# DM1098EMB_USB.net
KiCad netlist of a schematic drawn in Altium Designer
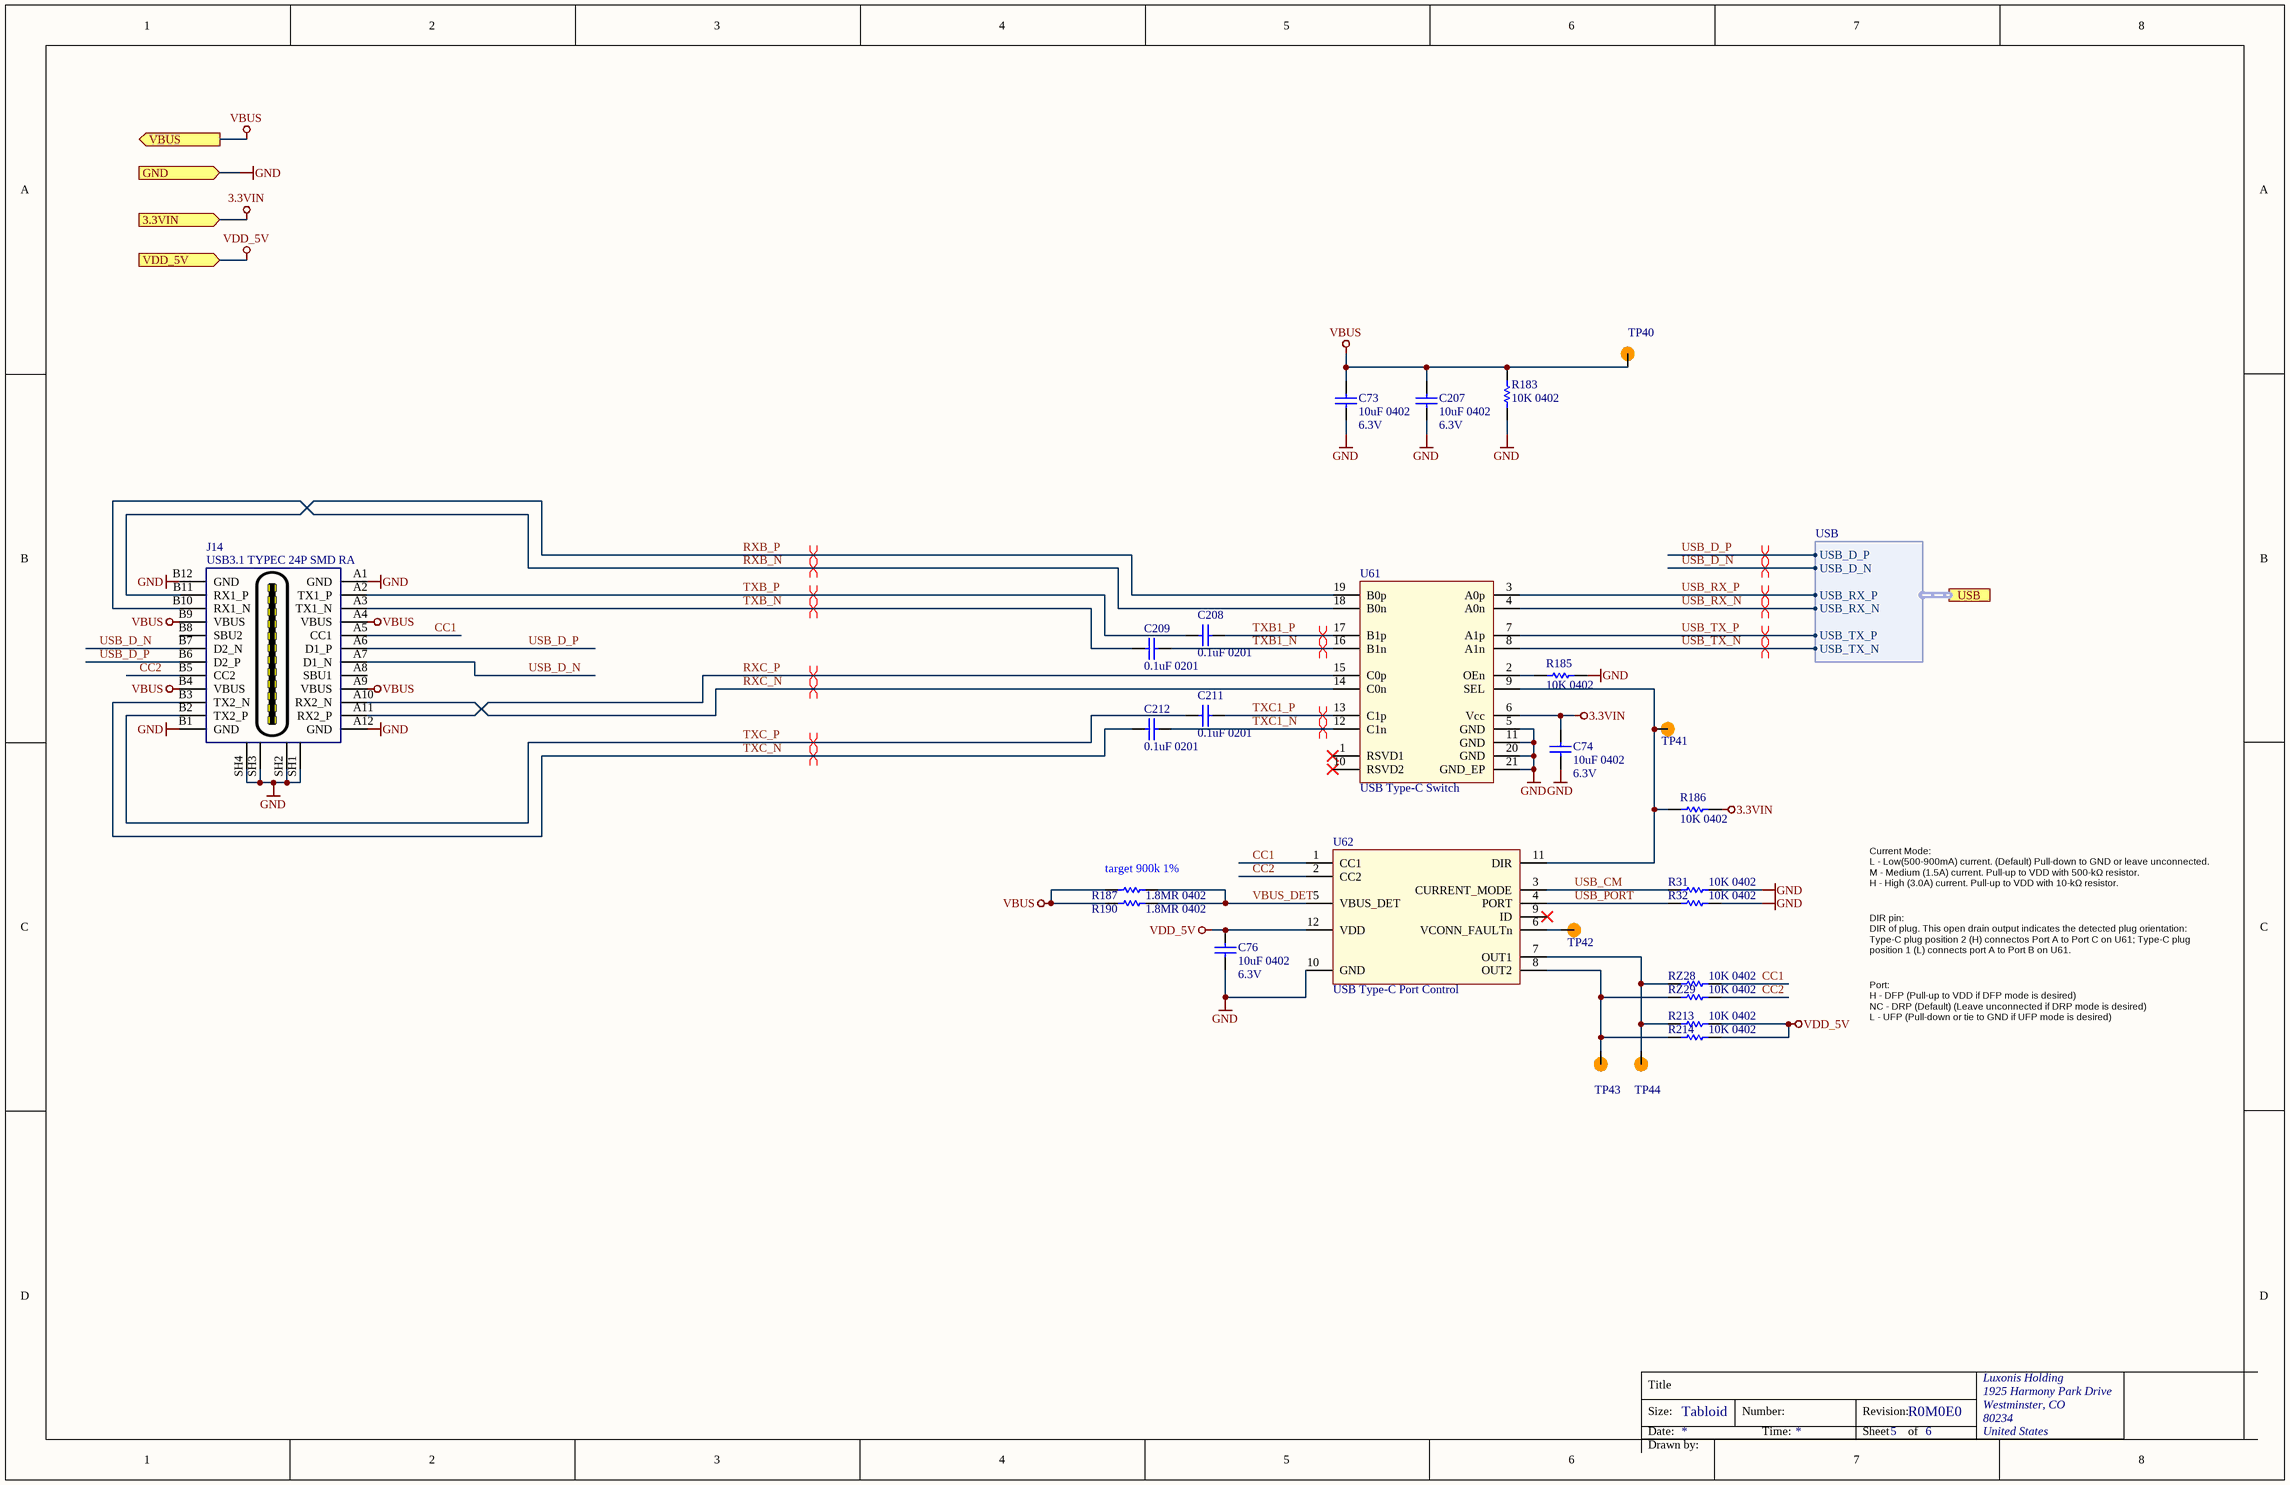
[diagram p0: DM1098EMB_USB.SchDoc]

(export (version "E")
  (design (tool "Eeschema 10.0.6"))
  (components
    (comp (ref "C73")
      (value "10uF 0402")
      (footprint "CAP_Altium_Vault_Generic:CAPC0402(1005)70_N")
      (description "CAP CER 10UF 6.3V X5R 0402 20%")
      (fields (field (name "TOLERANCE") "20%") (field (name "VOLTAGE RATING") "6.3V"))
      (libsource (lib "LuxonisMaster") (part "GRM155R60J106ME15D"))
    )
    (comp (ref "C74")
      (value "10uF 0402")
      (footprint "CAP_Altium_Vault_Generic:CAPC0402(1005)70_N")
      (description "CAP CER 10UF 6.3V X5R 0402 20%")
      (fields (field (name "TOLERANCE") "20%") (field (name "VOLTAGE RATING") "6.3V"))
      (libsource (lib "LuxonisMaster") (part "GRM155R60J106ME15D"))
    )
    (comp (ref "C76")
      (value "10uF 0402")
      (footprint "CAP_Altium_Vault_Generic:CAPC0402(1005)70_N")
      (description "CAP CER 10UF 6.3V X5R 0402 20%")
      (fields (field (name "TOLERANCE") "20%") (field (name "VOLTAGE RATING") "6.3V"))
      (libsource (lib "LuxonisMaster") (part "GRM155R60J106ME15D"))
    )
    (comp (ref "C207")
      (value "10uF 0402")
      (footprint "CAP_Altium_Vault_Generic:CAPC0402(1005)70_N")
      (description "CAP CER 10UF 6.3V X5R 0402 20%")
      (fields (field (name "TOLERANCE") "20%") (field (name "VOLTAGE RATING") "6.3V"))
      (libsource (lib "LuxonisMaster") (part "GRM155R60J106ME15D"))
    )
    (comp (ref "C208")
      (value "0.1uF 0201")
      (footprint "CAP_Altium_Vault_Generic:CAPC0201(0603)33_L")
      (description "CAP CER 0.1UF 10V X5R 0201")
      (fields (field (name "TOLERANCE") "10%") (field (name "VOLTAGE") "10V"))
      (libsource (lib "LuxonisMaster") (part "GRM033R61A104KE15D"))
    )
    (comp (ref "C209")
      (value "0.1uF 0201")
      (footprint "CAP_Altium_Vault_Generic:CAPC0201(0603)33_L")
      (description "CAP CER 0.1UF 10V X5R 0201")
      (fields (field (name "TOLERANCE") "10%") (field (name "VOLTAGE") "10V"))
      (libsource (lib "LuxonisMaster") (part "GRM033R61A104KE15D"))
    )
    (comp (ref "C211")
      (value "0.1uF 0201")
      (footprint "CAP_Altium_Vault_Generic:CAPC0201(0603)33_L")
      (description "CAP CER 0.1UF 10V X5R 0201")
      (fields (field (name "TOLERANCE") "10%") (field (name "VOLTAGE") "10V"))
      (libsource (lib "LuxonisMaster") (part "GRM033R61A104KE15D"))
    )
    (comp (ref "C212")
      (value "0.1uF 0201")
      (footprint "CAP_Altium_Vault_Generic:CAPC0201(0603)33_L")
      (description "CAP CER 0.1UF 10V X5R 0201")
      (fields (field (name "TOLERANCE") "10%") (field (name "VOLTAGE") "10V"))
      (libsource (lib "LuxonisMaster") (part "GRM033R61A104KE15D"))
    )
    (comp (ref "J14")
      (value "USB3.1 TYPEC 24P SMD RA")
      (footprint "LuxonisMaster:105450-0101")
      (description "CONN RCP USB3.1 TYPEC 24P SMD RA")
      (libsource (lib "LuxonisMaster") (part "105450-0101"))
    )
    (comp (ref "R31")
      (value "10K 0402")
      (footprint "RES_Altium_Vault_Generic:RESC0402(1005)_N")
      (fields (field (name "TOLERANCE") "1%"))
      (libsource (lib "LuxonisMaster") (part "RC0402FR-1310KL"))
    )
    (comp (ref "R32")
      (value "10K 0402")
      (footprint "RES_Altium_Vault_Generic:RESC0402(1005)_N")
      (fields (field (name "TOLERANCE") "1%"))
      (libsource (lib "LuxonisMaster") (part "RC0402FR-1310KL"))
    )
    (comp (ref "R183")
      (value "10K 0402")
      (footprint "RES_Altium_Vault_Generic:RESC0402(1005)_N")
      (fields (field (name "TOLERANCE") "1%"))
      (libsource (lib "LuxonisMaster") (part "RC0402FR-1310KL"))
    )
    (comp (ref "R185")
      (value "10K 0402")
      (footprint "RES_Altium_Vault_Generic:RESC0402(1005)_N")
      (fields (field (name "TOLERANCE") "1%"))
      (libsource (lib "LuxonisMaster") (part "RC0402FR-1310KL"))
    )
    (comp (ref "R186")
      (value "10K 0402")
      (footprint "RES_Altium_Vault_Generic:RESC0402(1005)_N")
      (fields (field (name "TOLERANCE") "1%"))
      (libsource (lib "LuxonisMaster") (part "RC0402FR-1310KL"))
    )
    (comp (ref "R187")
      (value "1.8MR 0402")
      (footprint "RES_Altium_Vault_Generic:RESC0402(1005)_N")
      (description "RES SMD 1.8M OHM 1% 1/16W 0402")
      (fields (field (name "TOLERANCE") "1%"))
      (libsource (lib "LuxonisMaster") (part "CRCW04021M80FKED"))
    )
    (comp (ref "R190")
      (value "1.8MR 0402")
      (footprint "RES_Altium_Vault_Generic:RESC0402(1005)_N")
      (description "RES SMD 1.8M OHM 1% 1/16W 0402")
      (fields (field (name "TOLERANCE") "1%"))
      (libsource (lib "LuxonisMaster") (part "CRCW04021M80FKED"))
    )
    (comp (ref "R213")
      (value "10K 0402")
      (footprint "RES_Altium_Vault_Generic:RESC0402(1005)_N")
      (fields (field (name "TOLERANCE") "1%"))
      (libsource (lib "LuxonisMaster") (part "RC0402FR-1310KL"))
    )
    (comp (ref "R214")
      (value "10K 0402")
      (footprint "RES_Altium_Vault_Generic:RESC0402(1005)_N")
      (fields (field (name "TOLERANCE") "1%"))
      (libsource (lib "LuxonisMaster") (part "RC0402FR-1310KL"))
    )
    (comp (ref "RZ28")
      (value "10K 0402")
      (footprint "RES_Altium_Vault_Generic:RESC0402(1005)_N")
      (fields (field (name "TOLERANCE") "1%"))
      (libsource (lib "LuxonisMaster") (part "RC0402FR-1310KL"))
    )
    (comp (ref "RZ29")
      (value "10K 0402")
      (footprint "RES_Altium_Vault_Generic:RESC0402(1005)_N")
      (fields (field (name "TOLERANCE") "1%"))
      (libsource (lib "LuxonisMaster") (part "RC0402FR-1310KL"))
    )
    (comp (ref "TP40")
      (value "TP100_200_NS")
      (footprint "LuxonisMaster:TP100_200_NS")
      (libsource (lib "LuxonisMaster") (part "TEST_POINT"))
    )
    (comp (ref "TP41")
      (value "TP100_200_NS")
      (footprint "LuxonisMaster:TP100_200_NS")
      (libsource (lib "LuxonisMaster") (part "TEST_POINT"))
    )
    (comp (ref "TP42")
      (value "TP100_200_NS")
      (footprint "LuxonisMaster:TP100_200_NS")
      (libsource (lib "LuxonisMaster") (part "TEST_POINT"))
    )
    (comp (ref "TP43")
      (value "TP100_200_NS")
      (footprint "LuxonisMaster:TP100_200_NS")
      (libsource (lib "LuxonisMaster") (part "TEST_POINT"))
    )
    (comp (ref "TP44")
      (value "TP100_200_NS")
      (footprint "LuxonisMaster:TP100_200_NS")
      (libsource (lib "LuxonisMaster") (part "TEST_POINT"))
    )
    (comp (ref "U61")
      (value "USB Type-C Switch")
      (footprint "LuxonisMaster:HD3SS3212RKSR")
      (description "IC MUX 2:1 8 OHM 20VQFN")
      (libsource (lib "LuxonisMaster") (part "HD3SS3212RKSR"))
    )
    (comp (ref "U62")
      (value "USB Type-C Port Control")
      (footprint "LuxonisMaster:TUSB321RWBR")
      (description "IC USB PORT CONTROL TYPE-C 12X2Q")
      (libsource (lib "LuxonisMaster") (part "TUSB321RWBR"))
    )
  )
  (nets
    (net (code "2") (name "/CC1") (class "Default")
      (node (ref "J14") (pin "A5") (pinfunction "CC1_A5") (pintype "passive"))
      (node (ref "RZ28") (pin "2") (pinfunction "2_2") (pintype "passive"))
      (node (ref "U62") (pin "1") (pinfunction "CC1_1") (pintype "passive"))
    )
    (net (code "3") (name "/CC2") (class "Default")
      (node (ref "J14") (pin "B5") (pinfunction "CC2_B5") (pintype "passive"))
      (node (ref "RZ29") (pin "2") (pinfunction "2_2") (pintype "passive"))
      (node (ref "U62") (pin "2") (pinfunction "CC2_2") (pintype "passive"))
    )
    (net (code "4") (name "/RXB_N") (class "Default")
      (node (ref "J14") (pin "B10") (pinfunction "RX1_N_B10") (pintype "passive"))
      (node (ref "U61") (pin "18") (pinfunction "B0n_18") (pintype "passive"))
    )
    (net (code "5") (name "/RXB_P") (class "Default")
      (node (ref "J14") (pin "B11") (pinfunction "RX1_P_B11") (pintype "passive"))
      (node (ref "U61") (pin "19") (pinfunction "B0p_19") (pintype "passive"))
    )
    (net (code "6") (name "/RXC_N") (class "Default")
      (node (ref "J14") (pin "A10") (pinfunction "RX2_N_A10") (pintype "passive"))
      (node (ref "U61") (pin "14") (pinfunction "C0n_14") (pintype "passive"))
    )
    (net (code "7") (name "/RXC_P") (class "Default")
      (node (ref "J14") (pin "A11") (pinfunction "RX2_P_A11") (pintype "passive"))
      (node (ref "U61") (pin "15") (pinfunction "C0p_15") (pintype "passive"))
    )
    (net (code "8") (name "/TXB1_N") (class "Default")
      (node (ref "C209") (pin "2") (pinfunction "2_2") (pintype "passive"))
      (node (ref "U61") (pin "16") (pinfunction "B1n_16") (pintype "passive"))
    )
    (net (code "9") (name "/TXB1_P") (class "Default")
      (node (ref "C208") (pin "2") (pinfunction "2_2") (pintype "passive"))
      (node (ref "U61") (pin "17") (pinfunction "B1p_17") (pintype "passive"))
    )
    (net (code "10") (name "/TXB_N") (class "Default")
      (node (ref "C209") (pin "1") (pinfunction "1_1") (pintype "passive"))
      (node (ref "J14") (pin "A3") (pinfunction "TX1_N_A3") (pintype "passive"))
    )
    (net (code "11") (name "/TXB_P") (class "Default")
      (node (ref "C208") (pin "1") (pinfunction "1_1") (pintype "passive"))
      (node (ref "J14") (pin "A2") (pinfunction "TX1_P_A2") (pintype "passive"))
    )
    (net (code "12") (name "/TXC1_N") (class "Default")
      (node (ref "C212") (pin "2") (pinfunction "2_2") (pintype "passive"))
      (node (ref "U61") (pin "12") (pinfunction "C1n_12") (pintype "passive"))
    )
    (net (code "13") (name "/TXC1_P") (class "Default")
      (node (ref "C211") (pin "2") (pinfunction "2_2") (pintype "passive"))
      (node (ref "U61") (pin "13") (pinfunction "C1p_13") (pintype "passive"))
    )
    (net (code "14") (name "/TXC_N") (class "Default")
      (node (ref "C212") (pin "1") (pinfunction "1_1") (pintype "passive"))
      (node (ref "J14") (pin "B3") (pinfunction "TX2_N_B3") (pintype "passive"))
    )
    (net (code "15") (name "/TXC_P") (class "Default")
      (node (ref "C211") (pin "1") (pinfunction "1_1") (pintype "passive"))
      (node (ref "J14") (pin "B2") (pinfunction "TX2_P_B2") (pintype "passive"))
    )
    (net (code "16") (name "/USB_CM") (class "Default")
      (node (ref "R31") (pin "1") (pinfunction "1_1") (pintype "passive"))
      (node (ref "U62") (pin "3") (pinfunction "CURRENT_MODE_3") (pintype "passive"))
    )
    (net (code "17") (name "/USB_D_N") (class "Default")
      (node (ref "J14") (pin "A7") (pinfunction "D1_N_A7") (pintype "passive"))
      (node (ref "J14") (pin "B7") (pinfunction "D2_N_B7") (pintype "passive"))
    )
    (net (code "18") (name "/USB_D_P") (class "Default")
      (node (ref "J14") (pin "A6") (pinfunction "D1_P_A6") (pintype "passive"))
      (node (ref "J14") (pin "B6") (pinfunction "D2_P_B6") (pintype "passive"))
    )
    (net (code "19") (name "/USB_PORT") (class "Default")
      (node (ref "R32") (pin "1") (pinfunction "1_1") (pintype "passive"))
      (node (ref "U62") (pin "4") (pinfunction "PORT_4") (pintype "passive"))
    )
    (net (code "20") (name "/USB_RX_N") (class "Default")
      (node (ref "U61") (pin "4") (pinfunction "A0n_4") (pintype "passive"))
    )
    (net (code "21") (name "/USB_RX_P") (class "Default")
      (node (ref "U61") (pin "3") (pinfunction "A0p_3") (pintype "passive"))
    )
    (net (code "22") (name "/USB_TX_N") (class "Default")
      (node (ref "U61") (pin "8") (pinfunction "A1n_8") (pintype "passive"))
    )
    (net (code "23") (name "/USB_TX_P") (class "Default")
      (node (ref "U61") (pin "7") (pinfunction "A1p_7") (pintype "passive"))
    )
    (net (code "24") (name "/VBUS_DET") (class "Default")
      (node (ref "R187") (pin "2") (pinfunction "2_2") (pintype "passive"))
      (node (ref "R190") (pin "2") (pinfunction "2_2") (pintype "passive"))
      (node (ref "U62") (pin "5") (pinfunction "VBUS_DET_5") (pintype "passive"))
    )
    (net (code "26") (name "3.3VIN") (class "Default")
      (node (ref "C74") (pin "2") (pinfunction "2_2") (pintype "passive"))
      (node (ref "R186") (pin "2") (pinfunction "2_2") (pintype "passive"))
      (node (ref "U61") (pin "6") (pinfunction "Vcc_6") (pintype "passive"))
    )
    (net (code "27") (name "GND") (class "Default")
      (node (ref "C207") (pin "1") (pinfunction "1_1") (pintype "passive"))
      (node (ref "C73") (pin "1") (pinfunction "1_1") (pintype "passive"))
      (node (ref "C74") (pin "1") (pinfunction "1_1") (pintype "passive"))
      (node (ref "C76") (pin "1") (pinfunction "1_1") (pintype "passive"))
      (node (ref "J14") (pin "A1") (pinfunction "GND_A1") (pintype "passive"))
      (node (ref "J14") (pin "A12") (pinfunction "GND_A12") (pintype "passive"))
      (node (ref "J14") (pin "B1") (pinfunction "GND_B1") (pintype "passive"))
      (node (ref "J14") (pin "B12") (pinfunction "GND_B12") (pintype "passive"))
      (node (ref "J14") (pin "SH1") (pinfunction "SH_SH1") (pintype "passive"))
      (node (ref "J14") (pin "SH2") (pinfunction "SH_SH2") (pintype "passive"))
      (node (ref "J14") (pin "SH3") (pinfunction "SH_SH3") (pintype "passive"))
      (node (ref "J14") (pin "SH4") (pinfunction "SH_SH4") (pintype "passive"))
      (node (ref "R183") (pin "1") (pinfunction "1_1") (pintype "passive"))
      (node (ref "R185") (pin "2") (pinfunction "2_2") (pintype "passive"))
      (node (ref "R31") (pin "2") (pinfunction "2_2") (pintype "passive"))
      (node (ref "R32") (pin "2") (pinfunction "2_2") (pintype "passive"))
      (node (ref "U61") (pin "11") (pinfunction "GND_11") (pintype "passive"))
      (node (ref "U61") (pin "20") (pinfunction "GND_20") (pintype "passive"))
      (node (ref "U61") (pin "21") (pinfunction "GND_EP_21") (pintype "passive"))
      (node (ref "U61") (pin "5") (pinfunction "GND_5") (pintype "passive"))
      (node (ref "U62") (pin "10") (pinfunction "GND_10") (pintype "passive"))
    )
    (net (code "28") (name "Net-(U61-OEn)") (class "Default")
      (node (ref "R185") (pin "1") (pinfunction "1_1") (pintype "passive"))
      (node (ref "U61") (pin "2") (pinfunction "OEn_2") (pintype "passive"))
    )
    (net (code "29") (name "Net-(U61-SEL)") (class "Default")
      (node (ref "R186") (pin "1") (pinfunction "1_1") (pintype "passive"))
      (node (ref "TP41") (pin "1") (pintype "passive"))
      (node (ref "U61") (pin "9") (pinfunction "SEL_9") (pintype "passive"))
      (node (ref "U62") (pin "11") (pinfunction "DIR_11") (pintype "passive"))
    )
    (net (code "30") (name "Net-(U62-OUT1)") (class "Default")
      (node (ref "R213") (pin "1") (pinfunction "1_1") (pintype "passive"))
      (node (ref "RZ28") (pin "1") (pinfunction "1_1") (pintype "passive"))
      (node (ref "TP44") (pin "1") (pintype "passive"))
      (node (ref "U62") (pin "7") (pinfunction "OUT1_7") (pintype "passive"))
    )
    (net (code "31") (name "Net-(U62-OUT2)") (class "Default")
      (node (ref "R214") (pin "1") (pinfunction "1_1") (pintype "passive"))
      (node (ref "RZ29") (pin "1") (pinfunction "1_1") (pintype "passive"))
      (node (ref "TP43") (pin "1") (pintype "passive"))
      (node (ref "U62") (pin "8") (pinfunction "OUT2_8") (pintype "passive"))
    )
    (net (code "32") (name "Net-(U62-VCONN_FAULTn)") (class "Default")
      (node (ref "TP42") (pin "1") (pintype "passive"))
      (node (ref "U62") (pin "6") (pinfunction "VCONN_FAULTn_6") (pintype "passive"))
    )
    (net (code "33") (name "VBUS") (class "Default")
      (node (ref "C207") (pin "2") (pinfunction "2_2") (pintype "passive"))
      (node (ref "C73") (pin "2") (pinfunction "2_2") (pintype "passive"))
      (node (ref "J14") (pin "A4") (pinfunction "VBUS_A4") (pintype "passive"))
      (node (ref "J14") (pin "A9") (pinfunction "VBUS_A9") (pintype "passive"))
      (node (ref "J14") (pin "B4") (pinfunction "VBUS_B4") (pintype "passive"))
      (node (ref "J14") (pin "B9") (pinfunction "VBUS_B9") (pintype "passive"))
      (node (ref "R183") (pin "2") (pinfunction "2_2") (pintype "passive"))
      (node (ref "R187") (pin "1") (pinfunction "1_1") (pintype "passive"))
      (node (ref "R190") (pin "1") (pinfunction "1_1") (pintype "passive"))
      (node (ref "TP40") (pin "1") (pintype "passive"))
    )
    (net (code "34") (name "VDD_5V") (class "Default")
      (node (ref "C76") (pin "2") (pinfunction "2_2") (pintype "passive"))
      (node (ref "R213") (pin "2") (pinfunction "2_2") (pintype "passive"))
      (node (ref "R214") (pin "2") (pinfunction "2_2") (pintype "passive"))
      (node (ref "U62") (pin "12") (pinfunction "VDD_12") (pintype "passive"))
    )
    (net (code "35") (name "unconnected-(J14-SBU1-PadA8)") (class "Default")
      (node (ref "J14") (pin "A8") (pinfunction "SBU1_A8") (pintype "passive"))
    )
    (net (code "36") (name "unconnected-(J14-SBU2-PadB8)") (class "Default")
      (node (ref "J14") (pin "B8") (pinfunction "SBU2_B8") (pintype "passive"))
    )
    (net (code "37") (name "unconnected-(U61-RSVD1-Pad1)") (class "Default")
      (node (ref "U61") (pin "1") (pinfunction "RSVD1_1") (pintype "passive+no_connect"))
    )
    (net (code "38") (name "unconnected-(U61-RSVD2-Pad10)") (class "Default")
      (node (ref "U61") (pin "10") (pinfunction "RSVD2_10") (pintype "passive+no_connect"))
    )
    (net (code "39") (name "unconnected-(U62-ID-Pad9)") (class "Default")
      (node (ref "U62") (pin "9") (pinfunction "ID_9") (pintype "passive+no_connect"))
    )
  )
)
